# Sheet1.net
KiCad netlist of a schematic drawn in Altium Designer
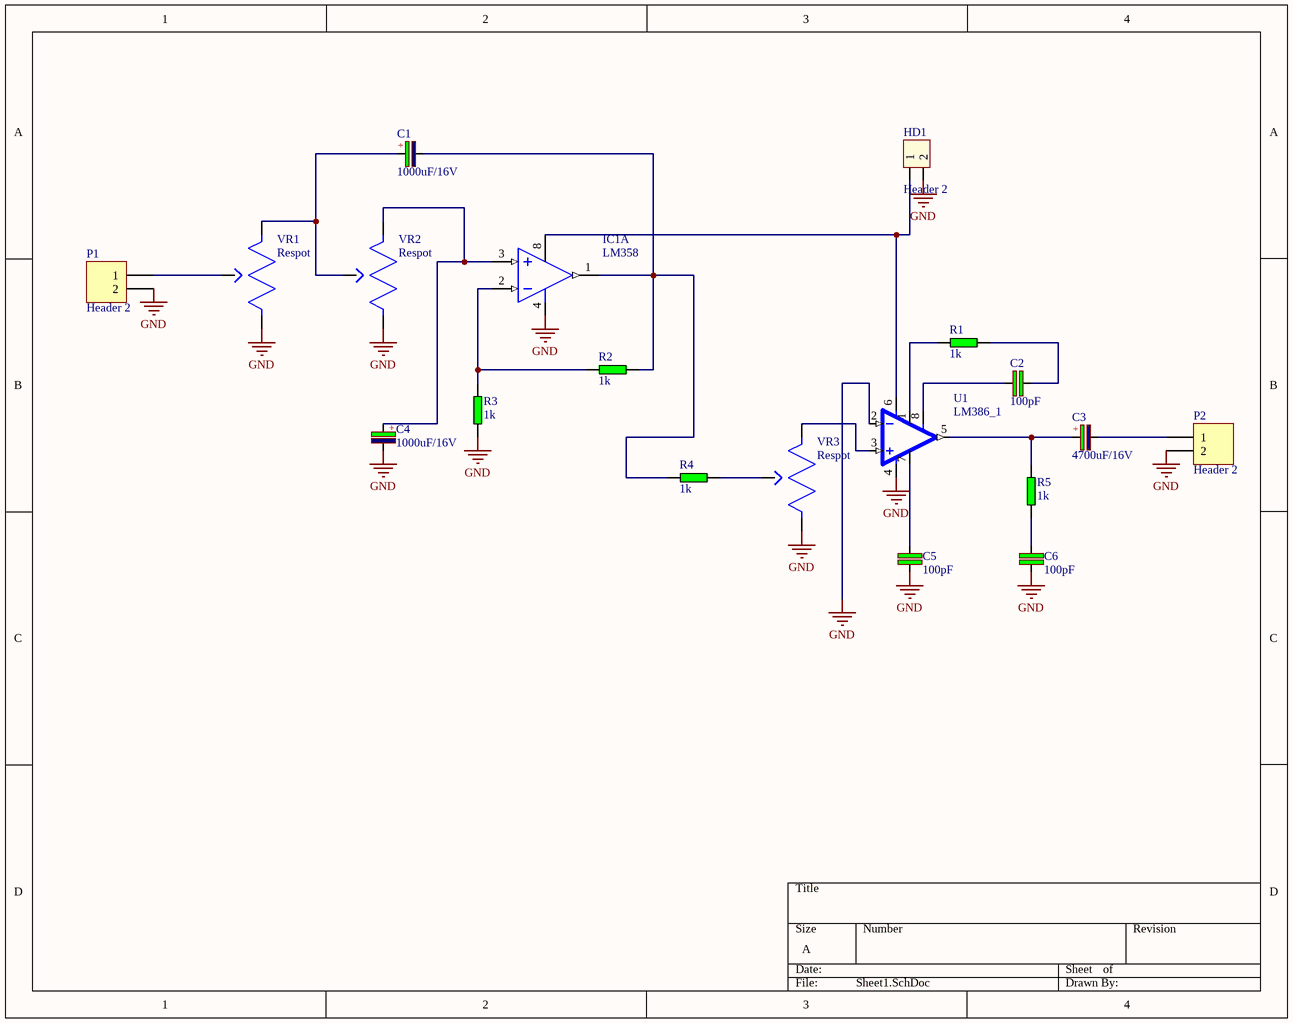
[diagram p0: Sheet1.SchDoc]

(export (version "E")
  (design (tool "Eeschema 10.0.6"))
  (components
    (comp (ref "C1")
      (value "1000uF/16V")
      (footprint "heromap:CP1.5/3.4")
      (description "Cap 1000uF/16V - 220uF/50V")
      (libsource (lib "heromap") (part "CP4"))
    )
    (comp (ref "C2")
      (value "100pF")
      (footprint "heromap:CN1")
      (description "Cap np  1pF - 472pF")
      (libsource (lib "") (part "CAP_1"))
    )
    (comp (ref "C3")
      (value "4700uF/16V")
      (footprint "heromap:CP3/7")
      (description "Cap 4700uF/16V - 2200uF/50V")
      (libsource (lib "heromap") (part "CP6"))
    )
    (comp (ref "C4")
      (value "1000uF/16V")
      (footprint "heromap:CP1.5/3.4")
      (description "Cap 1000uF/16V - 220uF/50V")
      (libsource (lib "") (part "CP4_1"))
    )
    (comp (ref "C5")
      (value "100pF")
      (footprint "heromap:CN1")
      (description "Cap np  1pF - 472pF")
      (libsource (lib "heromap") (part "CAP"))
    )
    (comp (ref "C6")
      (value "100pF")
      (footprint "heromap:CN1")
      (description "Cap np  1pF - 472pF")
      (libsource (lib "heromap") (part "CAP"))
    )
    (comp (ref "HD1")
      (value "Header 2")
      (footprint "heromap:HED2")
      (description "Header 2 (Green)")
      (libsource (lib "heromap") (part "Hed2"))
    )
    (comp (ref "IC1")
      (value "LM358")
      (footprint "heromap:DIP8/W0.3")
      (description "Low-Power Dual Operational Amplifier")
      (libsource (lib "heromap") (part "LM358"))
    )
    (comp (ref "P1")
      (value "Header 2")
      (footprint "heromap:HDR1X2")
      (description "Header, 2-Pin")
      (fields (field (name "PUBLISHER") "Altium Limited"))
      (libsource (lib "") (part "Header 2_1"))
    )
    (comp (ref "P2")
      (value "Header 2")
      (footprint "heromap:HDR1X2")
      (description "Header, 2-Pin")
      (fields (field (name "PUBLISHER") "Altium Limited"))
      (libsource (lib "heromap") (part "Header 2"))
    )
    (comp (ref "R1")
      (value "1k")
      (footprint "heromap:R1/4W")
      (description "Resistor 1/4W")
      (libsource (lib "heromap") (part "RES"))
    )
    (comp (ref "R2")
      (value "1k")
      (footprint "heromap:R1/4W")
      (description "Resistor 1/4W")
      (libsource (lib "heromap") (part "RES"))
    )
    (comp (ref "R3")
      (value "1k")
      (footprint "heromap:R1/4W")
      (description "Resistor 1/4W")
      (libsource (lib "") (part "RES_1"))
    )
    (comp (ref "R4")
      (value "1k")
      (footprint "heromap:R1/4W")
      (description "Resistor 1/4W")
      (libsource (lib "heromap") (part "RES"))
    )
    (comp (ref "R5")
      (value "1k")
      (footprint "heromap:R1/4W")
      (description "Resistor 1/4W")
      (libsource (lib "") (part "RES_1"))
    )
    (comp (ref "U1")
      (value "LM386_1")
      (footprint "lm386")
      (description "low voltage audio power amplifier")
      (fields (field (name "MP") "LM386"))
      (libsource (lib "heromap") (part "LM386_1"))
    )
    (comp (ref "VR1")
      (value "Respot")
      (footprint "Respot")
      (description "500k Ohm 1 Gang Linear Panel Mount Potentiometer None 1 Turn Conductive Plastic 0.2W, 1/5W PC Pins")
      (fields (field (name "MF") "TT Electronics/BI") (field (name "DIGI-KEY_PART_NUMBER") "987-1304-ND"))
      (libsource (lib "heromap") (part "Respot"))
    )
    (comp (ref "VR2")
      (value "Respot")
      (footprint "Respot")
      (description "500k Ohm 1 Gang Linear Panel Mount Potentiometer None 1 Turn Conductive Plastic 0.2W, 1/5W PC Pins")
      (fields (field (name "MF") "TT Electronics/BI") (field (name "DIGI-KEY_PART_NUMBER") "987-1304-ND"))
      (libsource (lib "heromap") (part "Respot"))
    )
    (comp (ref "VR3")
      (value "Respot")
      (footprint "Respot")
      (description "500k Ohm 1 Gang Linear Panel Mount Potentiometer None 1 Turn Conductive Plastic 0.2W, 1/5W PC Pins")
      (fields (field (name "MF") "TT Electronics/BI") (field (name "DIGI-KEY_PART_NUMBER") "987-1304-ND"))
      (libsource (lib "heromap") (part "Respot"))
    )
  )
  (nets
    (net (code "1") (name "GND") (class "Default")
      (node (ref "C4") (pin "2") (pinfunction "2_2") (pintype "passive"))
      (node (ref "C5") (pin "1") (pinfunction "1_1") (pintype "passive"))
      (node (ref "C6") (pin "1") (pinfunction "1_1") (pintype "passive"))
      (node (ref "HD1") (pin "2") (pinfunction "2_2") (pintype "passive"))
      (node (ref "IC1") (pin "4") (pinfunction "-V_4") (pintype "passive"))
      (node (ref "P1") (pin "2") (pinfunction "2_2") (pintype "passive"))
      (node (ref "P2") (pin "2") (pinfunction "2_2") (pintype "passive"))
      (node (ref "R3") (pin "1") (pinfunction "1_1") (pintype "passive"))
      (node (ref "U1") (pin "2") (pinfunction "-IN_2") (pintype "input"))
      (node (ref "U1") (pin "4") (pinfunction "V-_4") (pintype "power_in"))
      (node (ref "VR1") (pin "3") (pinfunction "3_3") (pintype "bidirectional"))
      (node (ref "VR2") (pin "3") (pinfunction "3_3") (pintype "bidirectional"))
      (node (ref "VR3") (pin "3") (pinfunction "3_3") (pintype "bidirectional"))
    )
    (net (code "2") (name "Net-(C1-Pad1)") (class "Default")
      (node (ref "C1") (pin "1") (pinfunction "1_1") (pintype "passive"))
      (node (ref "VR1") (pin "1") (pinfunction "1_1") (pintype "bidirectional"))
      (node (ref "VR2") (pin "2") (pinfunction "2_2") (pintype "bidirectional"))
    )
    (net (code "3") (name "Net-(C2-Pad2)") (class "Default")
      (node (ref "C2") (pin "2") (pinfunction "2_2") (pintype "passive"))
      (node (ref "R1") (pin "2") (pinfunction "2_2") (pintype "passive"))
    )
    (net (code "4") (name "Net-(C3-Pad2)") (class "Default")
      (node (ref "C3") (pin "2") (pinfunction "2_2") (pintype "passive"))
      (node (ref "P2") (pin "1") (pinfunction "1_1") (pintype "passive"))
    )
    (net (code "5") (name "Net-(C6-Pad2)") (class "Default")
      (node (ref "C6") (pin "2") (pinfunction "2_2") (pintype "passive"))
      (node (ref "R5") (pin "1") (pinfunction "1_1") (pintype "passive"))
    )
    (net (code "6") (name "Net-(IC1A-+V)") (class "Default")
      (node (ref "HD1") (pin "1") (pinfunction "1_1") (pintype "passive"))
      (node (ref "IC1") (pin "8") (pinfunction "+V_8") (pintype "passive"))
      (node (ref "U1") (pin "6") (pinfunction "V+_6") (pintype "power_in"))
    )
    (net (code "7") (name "Net-(IC1A-IN+)") (class "Default")
      (node (ref "C4") (pin "1") (pinfunction "1_1") (pintype "passive"))
      (node (ref "IC1") (pin "3") (pinfunction "IN+_3") (pintype "input"))
      (node (ref "VR2") (pin "1") (pinfunction "1_1") (pintype "bidirectional"))
    )
    (net (code "8") (name "Net-(IC1A-IN-)") (class "Default")
      (node (ref "IC1") (pin "2") (pinfunction "IN-_2") (pintype "input"))
      (node (ref "R2") (pin "1") (pinfunction "1_1") (pintype "passive"))
      (node (ref "R3") (pin "2") (pinfunction "2_2") (pintype "passive"))
    )
    (net (code "9") (name "Net-(IC1A-OUT)") (class "Default")
      (node (ref "C1") (pin "2") (pinfunction "2_2") (pintype "passive"))
      (node (ref "IC1") (pin "1") (pinfunction "OUT_1") (pintype "output"))
      (node (ref "R2") (pin "2") (pinfunction "2_2") (pintype "passive"))
      (node (ref "R4") (pin "1") (pinfunction "1_1") (pintype "passive"))
    )
    (net (code "10") (name "Net-(P1-Pad1)") (class "Default")
      (node (ref "P1") (pin "1") (pinfunction "1_1") (pintype "passive"))
      (node (ref "VR1") (pin "2") (pinfunction "2_2") (pintype "bidirectional"))
    )
    (net (code "11") (name "Net-(R4-Pad2)") (class "Default")
      (node (ref "R4") (pin "2") (pinfunction "2_2") (pintype "passive"))
      (node (ref "VR3") (pin "2") (pinfunction "2_2") (pintype "bidirectional"))
    )
    (net (code "12") (name "Net-(U1-+IN)") (class "Default")
      (node (ref "U1") (pin "3") (pinfunction "+IN_3") (pintype "input"))
      (node (ref "VR3") (pin "1") (pinfunction "1_1") (pintype "bidirectional"))
    )
    (net (code "13") (name "Net-(U1-BP)") (class "Default")
      (node (ref "C5") (pin "2") (pinfunction "2_2") (pintype "passive"))
      (node (ref "U1") (pin "7") (pinfunction "BP_7") (pintype "bidirectional"))
    )
    (net (code "14") (name "Net-(U1-GAIN@1)") (class "Default")
      (node (ref "R1") (pin "1") (pinfunction "1_1") (pintype "passive"))
      (node (ref "U1") (pin "1") (pinfunction "GAIN@1_1") (pintype "bidirectional"))
    )
    (net (code "15") (name "Net-(U1-GAIN@8)") (class "Default")
      (node (ref "C2") (pin "1") (pinfunction "1_1") (pintype "passive"))
      (node (ref "U1") (pin "8") (pinfunction "GAIN@8_8") (pintype "bidirectional"))
    )
    (net (code "16") (name "Net-(U1-OUT)") (class "Default")
      (node (ref "C3") (pin "1") (pinfunction "1_1") (pintype "passive"))
      (node (ref "R5") (pin "2") (pinfunction "2_2") (pintype "passive"))
      (node (ref "U1") (pin "5") (pinfunction "OUT_5") (pintype "output"))
    )
  )
)
